# ArdBir.net
KiCad netlist of a schematic drawn in EAGLE
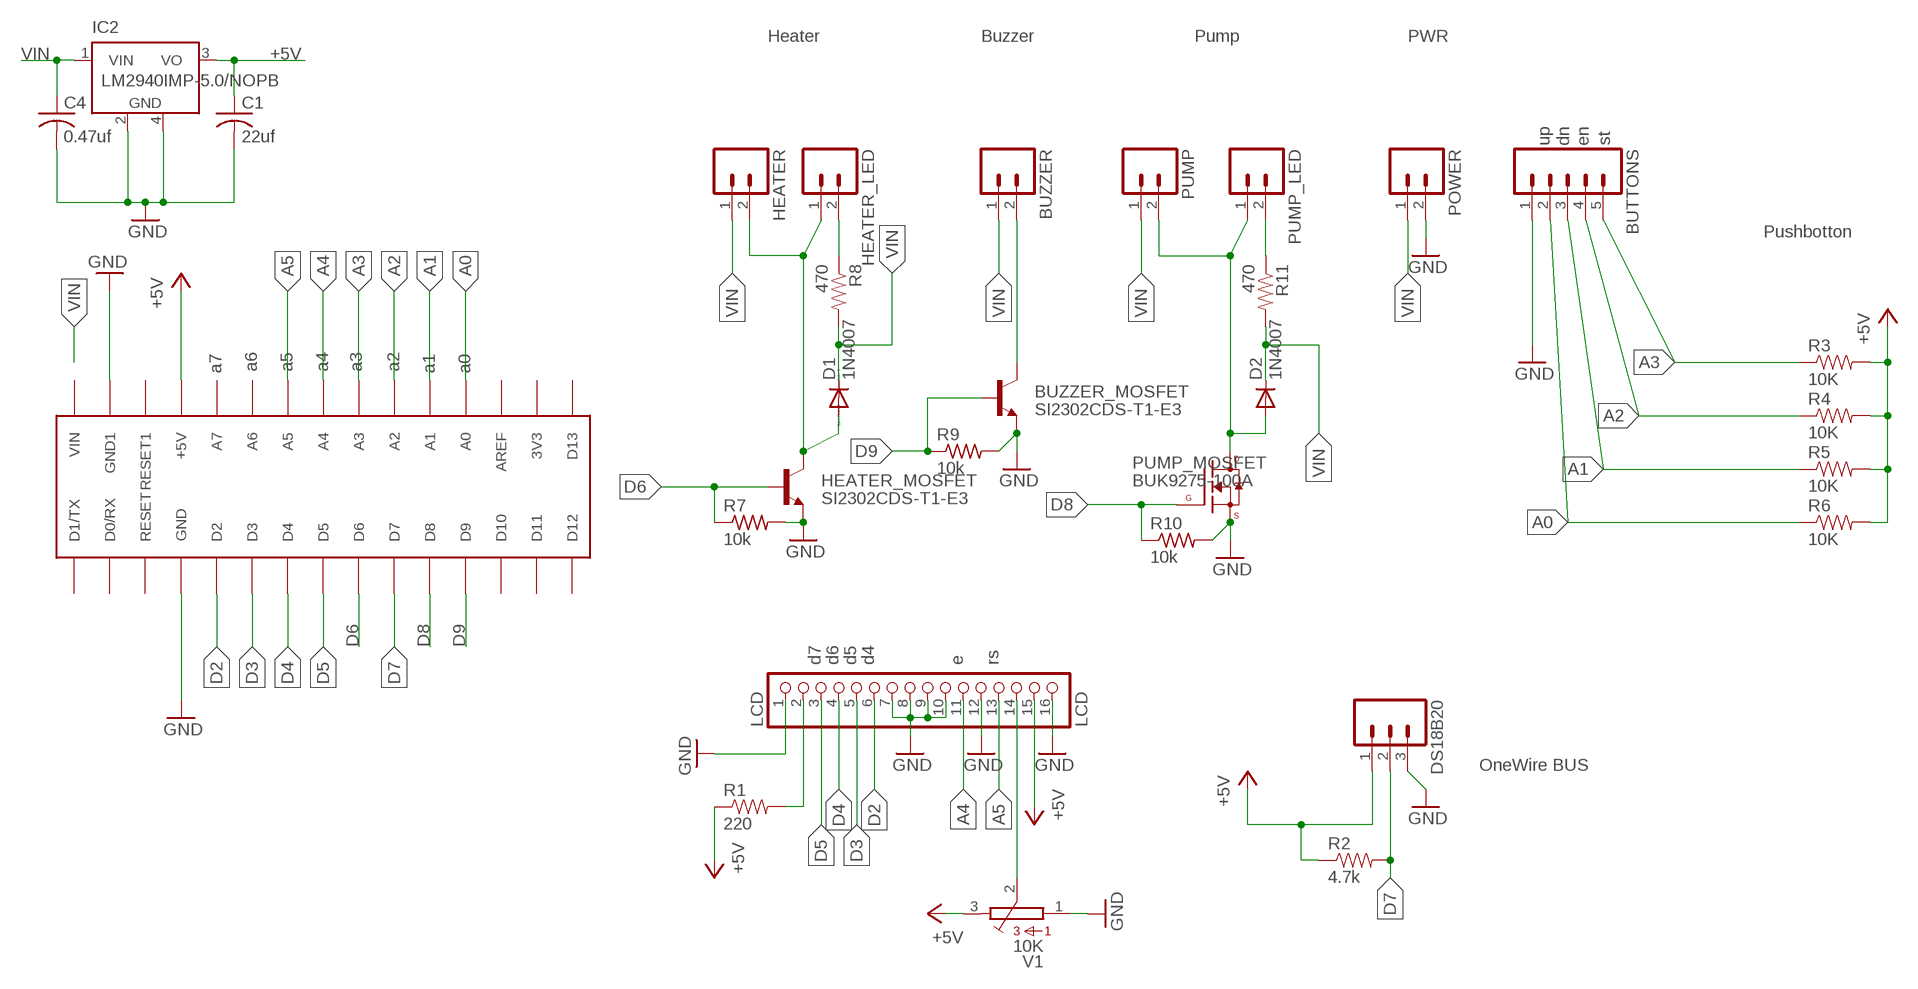
[diagram p0: schematic, sheet 1]

(export (version "E")
  (design (tool "Eeschema 10.0.6"))
  (components
    (comp (ref "BUTTONS")
      (value "M05LOCK")
      (footprint "eagle-import:1X05_LOCK")
      (libsource (lib "eagle-import") (part "M05LOCK"))
    )
    (comp (ref "BUZZER")
      (value "M02LOCK")
      (footprint "eagle-import:1X02_LOCK")
      (libsource (lib "eagle-import") (part "M02LOCK"))
    )
    (comp (ref "BUZZER_MOSFET")
      (value "SI2302CDS-T1-E3")
      (footprint "eagle-import:SOT23")
      (libsource (lib "eagle-import") (part "TRANSISTOR_NPNSOT23"))
    )
    (comp (ref "C1")
      (value "22uf")
      (footprint "eagle-import:C0805")
      (libsource (lib "eagle-import") (part "C-USC0805"))
    )
    (comp (ref "C4")
      (value "0.47uf")
      (footprint "eagle-import:C0805")
      (libsource (lib "eagle-import") (part "C-USC0805"))
    )
    (comp (ref "D1")
      (value "1N4007")
      (footprint "eagle-import:SOD-123_MINI-SMA")
      (libsource (lib "eagle-import") (part "CGRM400-G7"))
    )
    (comp (ref "D2")
      (value "1N4007")
      (footprint "eagle-import:SMB-DIODE")
      (libsource (lib "eagle-import") (part "DIODESMB"))
    )
    (comp (ref "DS18B20")
      (value "M03LONGPADS")
      (footprint "eagle-import:1X03_LONGPADS")
      (libsource (lib "eagle-import") (part "M03LONGPADS"))
    )
    (comp (ref "HEATER")
      (value "M023.5MM-NO_SILK")
      (footprint "eagle-import:SCREWTERMINAL-3.5MM-2-NS")
      (libsource (lib "eagle-import") (part "M023.5MM-NO_SILK"))
    )
    (comp (ref "HEATER_LED")
      (value "M02LOCK")
      (footprint "eagle-import:1X02_LOCK")
      (libsource (lib "eagle-import") (part "M02LOCK"))
    )
    (comp (ref "HEATER_MOSFET")
      (value "SI2302CDS-T1-E3")
      (footprint "eagle-import:SOT23")
      (libsource (lib "eagle-import") (part "TRANSISTOR_NPNSOT23"))
    )
    (comp (ref "IC2")
      (value "LM2940IMP-5.0/NOPB")
      (footprint "eagle-import:SOT223")
      (fields (field (name "MF") "NATIONAL SEMICONDUCTOR") (field (name "MPN") "LM2936MP-5.0/NOPB"))
      (libsource (lib "eagle-import") (part "LM2936MP?-5.0"))
    )
    (comp (ref "LCD")
      (value "LCD")
      (footprint "eagle-import:1X16")
      (libsource (lib "eagle-import") (part "PINHD-1X16"))
    )
    (comp (ref "POWER")
      (value "M023.5MM-NO_SILK")
      (footprint "eagle-import:SCREWTERMINAL-3.5MM-2-NS")
      (libsource (lib "eagle-import") (part "M023.5MM-NO_SILK"))
    )
    (comp (ref "PUMP")
      (value "M023.5MM-NO_SILK")
      (footprint "eagle-import:SCREWTERMINAL-3.5MM-2-NS")
      (libsource (lib "eagle-import") (part "M023.5MM-NO_SILK"))
    )
    (comp (ref "PUMP_LED")
      (value "M02LOCK")
      (footprint "eagle-import:1X02_LOCK")
      (libsource (lib "eagle-import") (part "M02LOCK"))
    )
    (comp (ref "PUMP_MOSFET")
      (value "BUK9275-100A")
      (footprint "eagle-import:DPAK")
      (libsource (lib "eagle-import") (part "BUK9275-100A"))
    )
    (comp (ref "R1")
      (value "220")
      (footprint "eagle-import:0805")
      (libsource (lib "eagle-import") (part "RESISTOR0805-RES"))
    )
    (comp (ref "R2")
      (value "4.7k")
      (footprint "eagle-import:0805")
      (libsource (lib "eagle-import") (part "RESISTOR0805-RES"))
    )
    (comp (ref "R3")
      (value "10K")
      (footprint "eagle-import:0805")
      (libsource (lib "eagle-import") (part "RESISTOR0805-RES"))
    )
    (comp (ref "R4")
      (value "10K")
      (footprint "eagle-import:0805")
      (libsource (lib "eagle-import") (part "RESISTOR0805-RES"))
    )
    (comp (ref "R5")
      (value "10K")
      (footprint "eagle-import:0805")
      (libsource (lib "eagle-import") (part "RESISTOR0805-RES"))
    )
    (comp (ref "R6")
      (value "10K")
      (footprint "eagle-import:0805")
      (libsource (lib "eagle-import") (part "RESISTOR0805-RES"))
    )
    (comp (ref "R7")
      (value "10k")
      (footprint "eagle-import:R0805")
      (libsource (lib "eagle-import") (part "R-US_R0805"))
    )
    (comp (ref "R8")
      (value "470")
      (footprint "eagle-import:0805")
      (libsource (lib "eagle-import") (part "RESISTOR0805-RES"))
    )
    (comp (ref "R9")
      (value "10k")
      (footprint "eagle-import:R0805")
      (libsource (lib "eagle-import") (part "R-US_R0805"))
    )
    (comp (ref "R10")
      (value "10k")
      (footprint "eagle-import:R0805")
      (libsource (lib "eagle-import") (part "R-US_R0805"))
    )
    (comp (ref "R11")
      (value "470")
      (footprint "eagle-import:0805")
      (libsource (lib "eagle-import") (part "RESISTOR0805-RES"))
    )
    (comp (ref "U$1")
      (value "ARDUINONANO")
      (footprint "eagle-import:PDIP-32")
      (libsource (lib "eagle-import") (part "ARDUINONANO"))
    )
    (comp (ref "V1")
      (value "10K")
      (footprint "eagle-import:CA9V")
      (libsource (lib "eagle-import") (part "CA9V"))
    )
  )
  (nets
    (net (code "1") (name "+5V") (class "Default")
      (node (ref "C1") (pin "1") (pinfunction "1_1") (pintype "passive"))
      (node (ref "DS18B20") (pin "1") (pinfunction "1_1") (pintype "passive"))
      (node (ref "IC2") (pin "3") (pinfunction "VO_3") (pintype "passive"))
      (node (ref "LCD") (pin "15") (pinfunction "15_15") (pintype "passive"))
      (node (ref "R1") (pin "1") (pinfunction "1_1") (pintype "passive"))
      (node (ref "R2") (pin "1") (pinfunction "1_1") (pintype "passive"))
      (node (ref "R3") (pin "2") (pinfunction "2_2") (pintype "passive"))
      (node (ref "R4") (pin "2") (pinfunction "2_2") (pintype "passive"))
      (node (ref "R5") (pin "2") (pinfunction "2_2") (pintype "passive"))
      (node (ref "R6") (pin "2") (pinfunction "2_2") (pintype "passive"))
      (node (ref "U$1") (pin "+5V") (pinfunction "+5V_+5V") (pintype "bidirectional"))
      (node (ref "V1") (pin "3") (pinfunction "3_3") (pintype "passive"))
    )
    (net (code "2") (name "A0") (class "Default")
      (node (ref "BUTTONS") (pin "2") (pinfunction "2_2") (pintype "passive"))
      (node (ref "R6") (pin "1") (pinfunction "1_1") (pintype "passive"))
      (node (ref "U$1") (pin "A0") (pinfunction "A0_A0") (pintype "bidirectional"))
    )
    (net (code "3") (name "A1") (class "Default")
      (node (ref "BUTTONS") (pin "3") (pinfunction "3_3") (pintype "passive"))
      (node (ref "R5") (pin "1") (pinfunction "1_1") (pintype "passive"))
      (node (ref "U$1") (pin "A1") (pinfunction "A1_A1") (pintype "bidirectional"))
    )
    (net (code "4") (name "A2") (class "Default")
      (node (ref "BUTTONS") (pin "4") (pinfunction "4_4") (pintype "passive"))
      (node (ref "R4") (pin "1") (pinfunction "1_1") (pintype "passive"))
      (node (ref "U$1") (pin "A2") (pinfunction "A2_A2") (pintype "bidirectional"))
    )
    (net (code "5") (name "A3") (class "Default")
      (node (ref "BUTTONS") (pin "5") (pinfunction "5_5") (pintype "passive"))
      (node (ref "R3") (pin "1") (pinfunction "1_1") (pintype "passive"))
      (node (ref "U$1") (pin "A3") (pinfunction "A3_A3") (pintype "bidirectional"))
    )
    (net (code "6") (name "A4") (class "Default")
      (node (ref "LCD") (pin "11") (pinfunction "11_11") (pintype "passive"))
      (node (ref "U$1") (pin "A4") (pinfunction "A4_A4") (pintype "bidirectional"))
    )
    (net (code "7") (name "A5") (class "Default")
      (node (ref "LCD") (pin "13") (pinfunction "13_13") (pintype "passive"))
      (node (ref "U$1") (pin "A5") (pinfunction "A5_A5") (pintype "bidirectional"))
    )
    (net (code "8") (name "D2") (class "Default")
      (node (ref "LCD") (pin "6") (pinfunction "6_6") (pintype "passive"))
      (node (ref "U$1") (pin "D2") (pinfunction "D2_D2") (pintype "bidirectional"))
    )
    (net (code "9") (name "D3") (class "Default")
      (node (ref "LCD") (pin "5") (pinfunction "5_5") (pintype "passive"))
      (node (ref "U$1") (pin "D3") (pinfunction "D3_D3") (pintype "bidirectional"))
    )
    (net (code "10") (name "D4") (class "Default")
      (node (ref "LCD") (pin "4") (pinfunction "4_4") (pintype "passive"))
      (node (ref "U$1") (pin "D4") (pinfunction "D4_D4") (pintype "bidirectional"))
    )
    (net (code "11") (name "D5") (class "Default")
      (node (ref "LCD") (pin "3") (pinfunction "3_3") (pintype "passive"))
      (node (ref "U$1") (pin "D5") (pinfunction "D5_D5") (pintype "bidirectional"))
    )
    (net (code "12") (name "D6") (class "Default")
      (node (ref "HEATER_MOSFET") (pin "1") (pinfunction "B_1") (pintype "passive"))
      (node (ref "R7") (pin "1") (pinfunction "1_1") (pintype "passive"))
      (node (ref "U$1") (pin "D6") (pinfunction "D6_D6") (pintype "bidirectional"))
    )
    (net (code "13") (name "D7") (class "Default")
      (node (ref "DS18B20") (pin "2") (pinfunction "2_2") (pintype "passive"))
      (node (ref "R2") (pin "2") (pinfunction "2_2") (pintype "passive"))
      (node (ref "U$1") (pin "D7") (pinfunction "D7_D7") (pintype "bidirectional"))
    )
    (net (code "14") (name "D8") (class "Default")
      (node (ref "PUMP_MOSFET") (pin "1") (pinfunction "G_1") (pintype "passive"))
      (node (ref "R10") (pin "1") (pinfunction "1_1") (pintype "passive"))
      (node (ref "U$1") (pin "D8") (pinfunction "D8_D8") (pintype "bidirectional"))
    )
    (net (code "15") (name "D9") (class "Default")
      (node (ref "BUZZER_MOSFET") (pin "1") (pinfunction "B_1") (pintype "passive"))
      (node (ref "R9") (pin "1") (pinfunction "1_1") (pintype "passive"))
      (node (ref "U$1") (pin "D9") (pinfunction "D9_D9") (pintype "bidirectional"))
    )
    (net (code "16") (name "GND") (class "Default")
      (node (ref "BUTTONS") (pin "1") (pinfunction "1_1") (pintype "passive"))
      (node (ref "BUZZER_MOSFET") (pin "2") (pinfunction "E_2") (pintype "passive"))
      (node (ref "C1") (pin "2") (pinfunction "2_2") (pintype "passive"))
      (node (ref "C4") (pin "2") (pinfunction "2_2") (pintype "passive"))
      (node (ref "DS18B20") (pin "3") (pinfunction "3_3") (pintype "passive"))
      (node (ref "HEATER_MOSFET") (pin "2") (pinfunction "E_2") (pintype "passive"))
      (node (ref "IC2") (pin "2") (pinfunction "GND_2") (pintype "passive"))
      (node (ref "IC2") (pin "4") (pinfunction "GND_4") (pintype "passive"))
      (node (ref "LCD") (pin "1") (pinfunction "1_1") (pintype "passive"))
      (node (ref "LCD") (pin "10") (pinfunction "10_10") (pintype "passive"))
      (node (ref "LCD") (pin "12") (pinfunction "12_12") (pintype "passive"))
      (node (ref "LCD") (pin "16") (pinfunction "16_16") (pintype "passive"))
      (node (ref "LCD") (pin "7") (pinfunction "7_7") (pintype "passive"))
      (node (ref "LCD") (pin "8") (pinfunction "8_8") (pintype "passive"))
      (node (ref "LCD") (pin "9") (pinfunction "9_9") (pintype "passive"))
      (node (ref "POWER") (pin "2") (pinfunction "2_2") (pintype "passive"))
      (node (ref "PUMP_MOSFET") (pin "3") (pinfunction "S_3") (pintype "passive"))
      (node (ref "R10") (pin "2") (pinfunction "2_2") (pintype "passive"))
      (node (ref "R7") (pin "2") (pinfunction "2_2") (pintype "passive"))
      (node (ref "R9") (pin "2") (pinfunction "2_2") (pintype "passive"))
      (node (ref "U$1") (pin "GND") (pinfunction "GND_GND") (pintype "bidirectional"))
      (node (ref "U$1") (pin "GND1") (pinfunction "GND1_GND1") (pintype "bidirectional"))
      (node (ref "V1") (pin "1") (pinfunction "1_1") (pintype "passive"))
    )
    (net (code "17") (name "Net-(BUZZER_MOSFET-C)") (class "Default")
      (node (ref "BUZZER") (pin "2") (pinfunction "2_2") (pintype "passive"))
      (node (ref "BUZZER_MOSFET") (pin "3") (pinfunction "C_3") (pintype "passive"))
    )
    (net (code "18") (name "Net-(HEATER_LED-Pad2)") (class "Default")
      (node (ref "HEATER_LED") (pin "2") (pinfunction "2_2") (pintype "passive"))
      (node (ref "R8") (pin "1") (pinfunction "1_1") (pintype "passive"))
    )
    (net (code "19") (name "Net-(HEATER_MOSFET-C)") (class "Default")
      (node (ref "D1") (pin "A") (pinfunction "A_A") (pintype "passive"))
      (node (ref "HEATER") (pin "2") (pinfunction "2_2") (pintype "passive"))
      (node (ref "HEATER_LED") (pin "1") (pinfunction "1_1") (pintype "passive"))
      (node (ref "HEATER_MOSFET") (pin "3") (pinfunction "C_3") (pintype "passive"))
    )
    (net (code "20") (name "Net-(LCD-Pad2)") (class "Default")
      (node (ref "LCD") (pin "2") (pinfunction "2_2") (pintype "passive"))
      (node (ref "R1") (pin "2") (pinfunction "2_2") (pintype "passive"))
    )
    (net (code "21") (name "Net-(LCD-Pad14)") (class "Default")
      (node (ref "LCD") (pin "14") (pinfunction "14_14") (pintype "passive"))
      (node (ref "V1") (pin "2") (pinfunction "2_2") (pintype "passive"))
    )
    (net (code "22") (name "Net-(PUMP_LED-Pad2)") (class "Default")
      (node (ref "PUMP_LED") (pin "2") (pinfunction "2_2") (pintype "passive"))
      (node (ref "R11") (pin "1") (pinfunction "1_1") (pintype "passive"))
    )
    (net (code "23") (name "Net-(PUMP_MOSFET-D)") (class "Default")
      (node (ref "D2") (pin "A") (pinfunction "A_A") (pintype "passive"))
      (node (ref "PUMP") (pin "2") (pinfunction "2_2") (pintype "passive"))
      (node (ref "PUMP_LED") (pin "1") (pinfunction "1_1") (pintype "passive"))
      (node (ref "PUMP_MOSFET") (pin "4") (pinfunction "D_4") (pintype "passive"))
    )
    (net (code "24") (name "VIN") (class "Default")
      (node (ref "BUZZER") (pin "1") (pinfunction "1_1") (pintype "passive"))
      (node (ref "C4") (pin "1") (pinfunction "1_1") (pintype "passive"))
      (node (ref "D1") (pin "C") (pinfunction "C_C") (pintype "passive"))
      (node (ref "D2") (pin "C") (pinfunction "C_C") (pintype "passive"))
      (node (ref "HEATER") (pin "1") (pinfunction "1_1") (pintype "passive"))
      (node (ref "IC2") (pin "1") (pinfunction "VIN_1") (pintype "input"))
      (node (ref "POWER") (pin "1") (pinfunction "1_1") (pintype "passive"))
      (node (ref "PUMP") (pin "1") (pinfunction "1_1") (pintype "passive"))
      (node (ref "R11") (pin "2") (pinfunction "2_2") (pintype "passive"))
      (node (ref "R8") (pin "2") (pinfunction "2_2") (pintype "passive"))
    )
    (net (code "25") (name "unconnected-(U$1-Pad3V3)") (class "Default")
      (node (ref "U$1") (pin "3V3") (pinfunction "3V3_3V3") (pintype "bidirectional"))
    )
    (net (code "26") (name "unconnected-(U$1-PadA6)") (class "Default")
      (node (ref "U$1") (pin "A6") (pinfunction "A6_A6") (pintype "bidirectional"))
    )
    (net (code "27") (name "unconnected-(U$1-PadA7)") (class "Default")
      (node (ref "U$1") (pin "A7") (pinfunction "A7_A7") (pintype "bidirectional"))
    )
    (net (code "28") (name "unconnected-(U$1-PadAREF)") (class "Default")
      (node (ref "U$1") (pin "AREF") (pinfunction "AREF_AREF") (pintype "bidirectional"))
    )
    (net (code "29") (name "unconnected-(U$1-PadD0{slash}RX)") (class "Default")
      (node (ref "U$1") (pin "D0/RX") (pinfunction "D0/RX_D0/RX") (pintype "bidirectional"))
    )
    (net (code "30") (name "unconnected-(U$1-PadD1{slash}TX)") (class "Default")
      (node (ref "U$1") (pin "D1/TX") (pinfunction "D1/TX_D1/TX") (pintype "bidirectional"))
    )
    (net (code "31") (name "unconnected-(U$1-PadD10)") (class "Default")
      (node (ref "U$1") (pin "D10") (pinfunction "D10_D10") (pintype "bidirectional"))
    )
    (net (code "32") (name "unconnected-(U$1-PadD11)") (class "Default")
      (node (ref "U$1") (pin "D11") (pinfunction "D11_D11") (pintype "bidirectional"))
    )
    (net (code "33") (name "unconnected-(U$1-PadD12)") (class "Default")
      (node (ref "U$1") (pin "D12") (pinfunction "D12_D12") (pintype "bidirectional"))
    )
    (net (code "34") (name "unconnected-(U$1-PadD13)") (class "Default")
      (node (ref "U$1") (pin "D13") (pinfunction "D13_D13") (pintype "bidirectional"))
    )
    (net (code "35") (name "unconnected-(U$1-PadRESET)") (class "Default")
      (node (ref "U$1") (pin "RESET") (pinfunction "RESET_RESET") (pintype "bidirectional"))
    )
    (net (code "36") (name "unconnected-(U$1-PadRESET1)") (class "Default")
      (node (ref "U$1") (pin "RESET1") (pinfunction "RESET1_RESET1") (pintype "bidirectional"))
    )
    (net (code "37") (name "unconnected-(U$1-PadVIN)") (class "Default")
      (node (ref "U$1") (pin "VIN") (pinfunction "VIN_VIN") (pintype "bidirectional"))
    )
  )
)
